# easyeda.net
KiCad netlist of a schematic drawn in EasyEDA
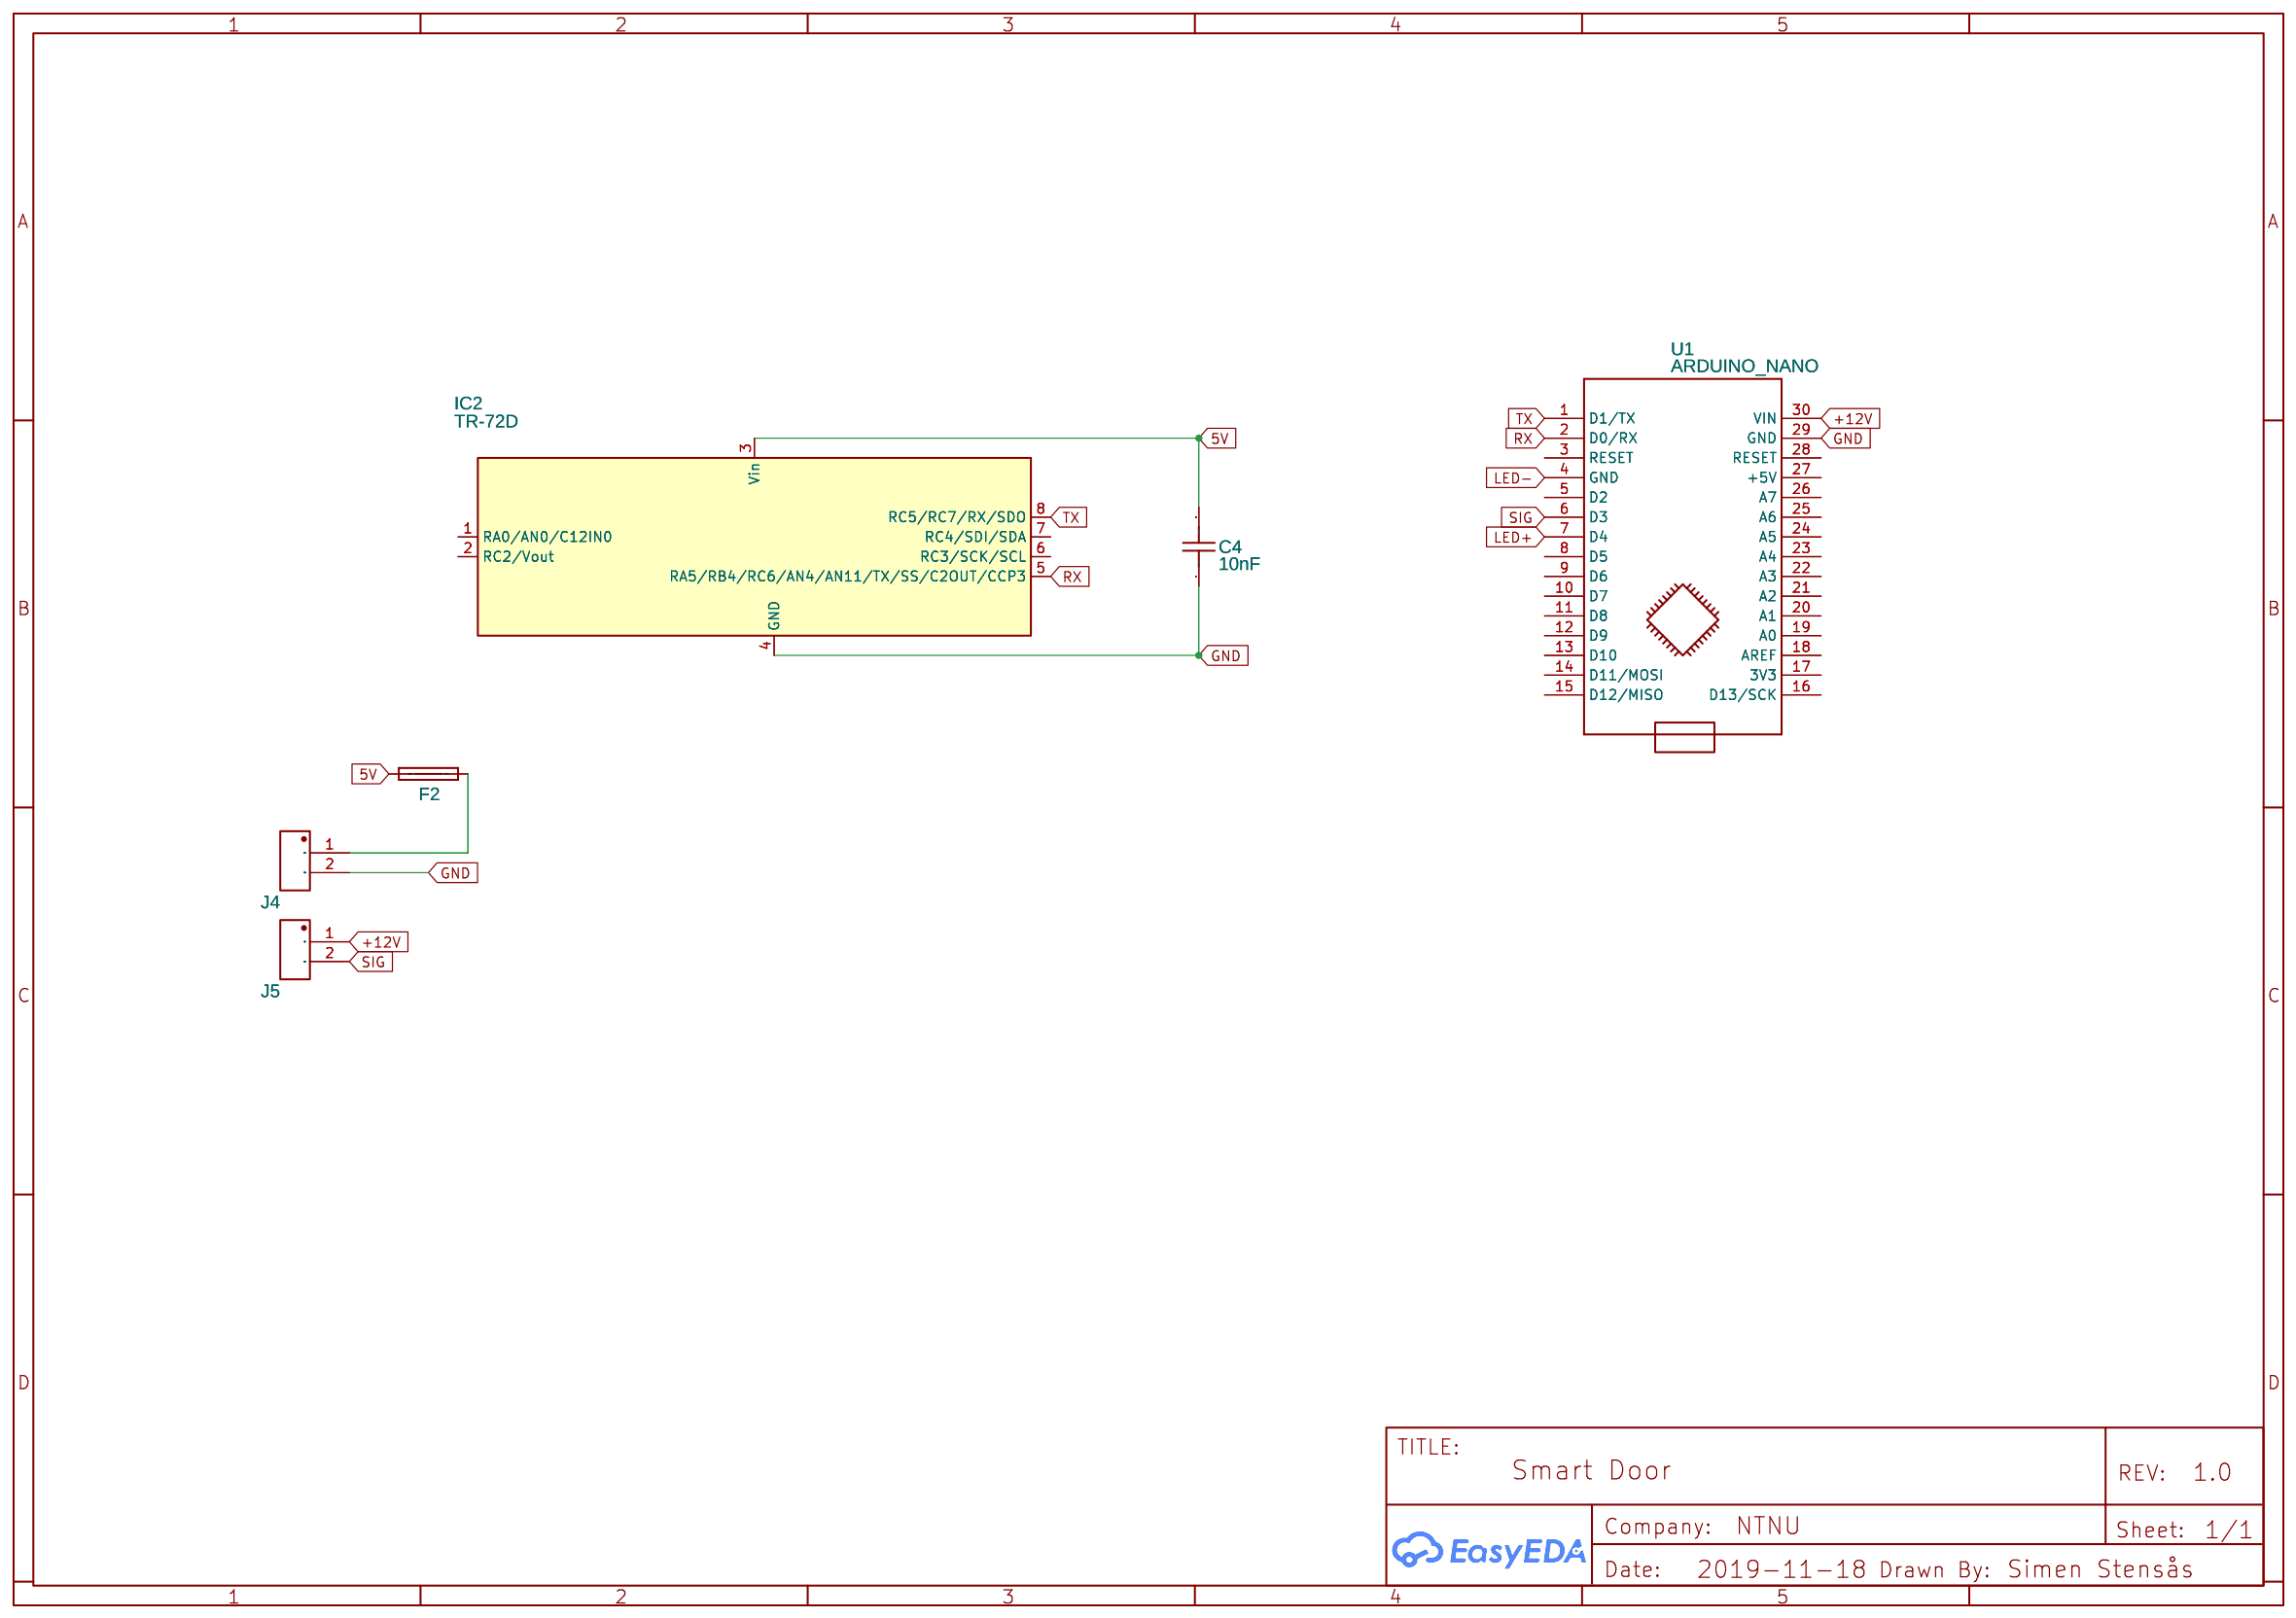
[diagram p0: schematic sheet]

(export (version "E")
  (design (tool "Eeschema 10.0.6"))
  (components
    (comp (ref "C4")
      (value "10nF")
      (fields
        (field (name "BOM_Manufacturer Part") "0603B103K500AT")
        (field (name "BOM_Supplier Part") "C327421")
      )
      (libsource (lib "") (part "0603B103K500AT"))
    )
    (comp (ref "F2")
      (value "NO")
      (fields
        (field (name "BOM_Manufacturer Part") "3403.0015.11")
        (field (name "BOM_Supplier Part") "693-3403.0015.11")
      )
      (libsource (lib "") (part "Unknown_215_375"))
    )
    (comp (ref "IC2") (value "TR-72D") (libsource (lib "") (part "Unknown_235_265")))
    (comp (ref "J4")
      (value "KF127_2P_5.08")
      (fields (field (name "BOM_Manufacturer Part") "KF127L-5.08"))
      (libsource (lib "") (part "Unknown_155_430"))
    )
    (comp (ref "J5")
      (value "KF127_2P_5.08")
      (fields (field (name "BOM_Manufacturer Part") "KF127L-5.08"))
      (libsource (lib "") (part "Unknown_155_475"))
    )
    (comp (ref "U1") (value "ARDUINO_NANO") (libsource (lib "") (part "Unknown_845_280")))
  )
  (nets
    (net (code "1") (name "+12V") (class "Default")
      (node (ref "J5") (pin "1") (pinfunction "PIN1_1") (pintype "unspecified"))
      (node (ref "U1") (pin "30") (pinfunction "VIN_30") (pintype "unspecified"))
    )
    (net (code "2") (name "5V") (class "Default")
      (node (ref "C4") (pin "2") (pinfunction "2_2") (pintype "unspecified"))
      (node (ref "F2") (pin "1") (pinfunction "1_1") (pintype "bidirectional"))
      (node (ref "IC2") (pin "3") (pinfunction "Vin_3") (pintype "bidirectional"))
    )
    (net (code "3") (name "GND") (class "Default")
      (node (ref "C4") (pin "1") (pinfunction "1_1") (pintype "unspecified"))
      (node (ref "IC2") (pin "4") (pinfunction "GND_4") (pintype "bidirectional"))
      (node (ref "J4") (pin "2") (pinfunction "PIN2_2") (pintype "unspecified"))
      (node (ref "U1") (pin "29") (pinfunction "GND_29") (pintype "unspecified"))
    )
    (net (code "4") (name "LED+") (class "Default")
      (node (ref "U1") (pin "7") (pinfunction "D4_7") (pintype "unspecified"))
    )
    (net (code "5") (name "LED-") (class "Default")
      (node (ref "U1") (pin "4") (pinfunction "GND_4") (pintype "unspecified"))
    )
    (net (code "6") (name "Net-(J4-PIN1)") (class "Default")
      (node (ref "F2") (pin "2") (pinfunction "2_2") (pintype "bidirectional"))
      (node (ref "J4") (pin "1") (pinfunction "PIN1_1") (pintype "unspecified"))
    )
    (net (code "7") (name "RX") (class "Default")
      (node (ref "IC2") (pin "5") (pinfunction "RA5/RB4/RC6/AN4/AN11/TX/SS/C2OUT/CCP3_5") (pintype "bidirectional"))
      (node (ref "U1") (pin "2") (pinfunction "D0/RX_2") (pintype "unspecified"))
    )
    (net (code "8") (name "SIG") (class "Default")
      (node (ref "J5") (pin "2") (pinfunction "PIN2_2") (pintype "unspecified"))
      (node (ref "U1") (pin "6") (pinfunction "D3_6") (pintype "unspecified"))
    )
    (net (code "9") (name "TX") (class "Default")
      (node (ref "IC2") (pin "8") (pinfunction "RC5/RC7/RX/SDO_8") (pintype "bidirectional"))
      (node (ref "U1") (pin "1") (pinfunction "D1/TX_1") (pintype "unspecified"))
    )
    (net (code "10") (name "unconnected-(IC2-RA0{slash}AN0{slash}C12IN0-Pad1)") (class "Default")
      (node (ref "IC2") (pin "1") (pinfunction "RA0/AN0/C12IN0_1") (pintype "bidirectional"))
    )
    (net (code "11") (name "unconnected-(IC2-RC2{slash}Vout-Pad2)") (class "Default")
      (node (ref "IC2") (pin "2") (pinfunction "RC2/Vout_2") (pintype "bidirectional"))
    )
    (net (code "12") (name "unconnected-(IC2-RC3{slash}SCK{slash}SCL-Pad6)") (class "Default")
      (node (ref "IC2") (pin "6") (pinfunction "RC3/SCK/SCL_6") (pintype "bidirectional"))
    )
    (net (code "13") (name "unconnected-(IC2-RC4{slash}SDI{slash}SDA-Pad7)") (class "Default")
      (node (ref "IC2") (pin "7") (pinfunction "RC4/SDI/SDA_7") (pintype "bidirectional"))
    )
    (net (code "14") (name "unconnected-(U1-+5V-Pad27)") (class "Default")
      (node (ref "U1") (pin "27") (pinfunction "+5V_27") (pintype "unspecified"))
    )
    (net (code "15") (name "unconnected-(U1-3V3-Pad17)") (class "Default")
      (node (ref "U1") (pin "17") (pinfunction "3V3_17") (pintype "unspecified"))
    )
    (net (code "16") (name "unconnected-(U1-A0-Pad19)") (class "Default")
      (node (ref "U1") (pin "19") (pinfunction "A0_19") (pintype "unspecified"))
    )
    (net (code "17") (name "unconnected-(U1-A1-Pad20)") (class "Default")
      (node (ref "U1") (pin "20") (pinfunction "A1_20") (pintype "unspecified"))
    )
    (net (code "18") (name "unconnected-(U1-A2-Pad21)") (class "Default")
      (node (ref "U1") (pin "21") (pinfunction "A2_21") (pintype "unspecified"))
    )
    (net (code "19") (name "unconnected-(U1-A3-Pad22)") (class "Default")
      (node (ref "U1") (pin "22") (pinfunction "A3_22") (pintype "unspecified"))
    )
    (net (code "20") (name "unconnected-(U1-A4-Pad23)") (class "Default")
      (node (ref "U1") (pin "23") (pinfunction "A4_23") (pintype "unspecified"))
    )
    (net (code "21") (name "unconnected-(U1-A5-Pad24)") (class "Default")
      (node (ref "U1") (pin "24") (pinfunction "A5_24") (pintype "unspecified"))
    )
    (net (code "22") (name "unconnected-(U1-A6-Pad25)") (class "Default")
      (node (ref "U1") (pin "25") (pinfunction "A6_25") (pintype "unspecified"))
    )
    (net (code "23") (name "unconnected-(U1-A7-Pad26)") (class "Default")
      (node (ref "U1") (pin "26") (pinfunction "A7_26") (pintype "unspecified"))
    )
    (net (code "24") (name "unconnected-(U1-AREF-Pad18)") (class "Default")
      (node (ref "U1") (pin "18") (pinfunction "AREF_18") (pintype "unspecified"))
    )
    (net (code "25") (name "unconnected-(U1-D2-Pad5)") (class "Default")
      (node (ref "U1") (pin "5") (pinfunction "D2_5") (pintype "unspecified"))
    )
    (net (code "26") (name "unconnected-(U1-D5-Pad8)") (class "Default")
      (node (ref "U1") (pin "8") (pinfunction "D5_8") (pintype "unspecified"))
    )
    (net (code "27") (name "unconnected-(U1-D6-Pad9)") (class "Default")
      (node (ref "U1") (pin "9") (pinfunction "D6_9") (pintype "unspecified"))
    )
    (net (code "28") (name "unconnected-(U1-D7-Pad10)") (class "Default")
      (node (ref "U1") (pin "10") (pinfunction "D7_10") (pintype "unspecified"))
    )
    (net (code "29") (name "unconnected-(U1-D8-Pad11)") (class "Default")
      (node (ref "U1") (pin "11") (pinfunction "D8_11") (pintype "unspecified"))
    )
    (net (code "30") (name "unconnected-(U1-D9-Pad12)") (class "Default")
      (node (ref "U1") (pin "12") (pinfunction "D9_12") (pintype "unspecified"))
    )
    (net (code "31") (name "unconnected-(U1-D10-Pad13)") (class "Default")
      (node (ref "U1") (pin "13") (pinfunction "D10_13") (pintype "unspecified"))
    )
    (net (code "32") (name "unconnected-(U1-D11{slash}MOSI-Pad14)") (class "Default")
      (node (ref "U1") (pin "14") (pinfunction "D11/MOSI_14") (pintype "unspecified"))
    )
    (net (code "33") (name "unconnected-(U1-D12{slash}MISO-Pad15)") (class "Default")
      (node (ref "U1") (pin "15") (pinfunction "D12/MISO_15") (pintype "unspecified"))
    )
    (net (code "34") (name "unconnected-(U1-D13{slash}SCK-Pad16)") (class "Default")
      (node (ref "U1") (pin "16") (pinfunction "D13/SCK_16") (pintype "unspecified"))
    )
    (net (code "35") (name "unconnected-(U1-RESET-Pad3)") (class "Default")
      (node (ref "U1") (pin "3") (pinfunction "RESET_3") (pintype "unspecified"))
    )
    (net (code "36") (name "unconnected-(U1-RESET-Pad28)") (class "Default")
      (node (ref "U1") (pin "28") (pinfunction "RESET_28") (pintype "unspecified"))
    )
  )
)
